# keybored.net
KiCad netlist of a schematic drawn in EAGLE
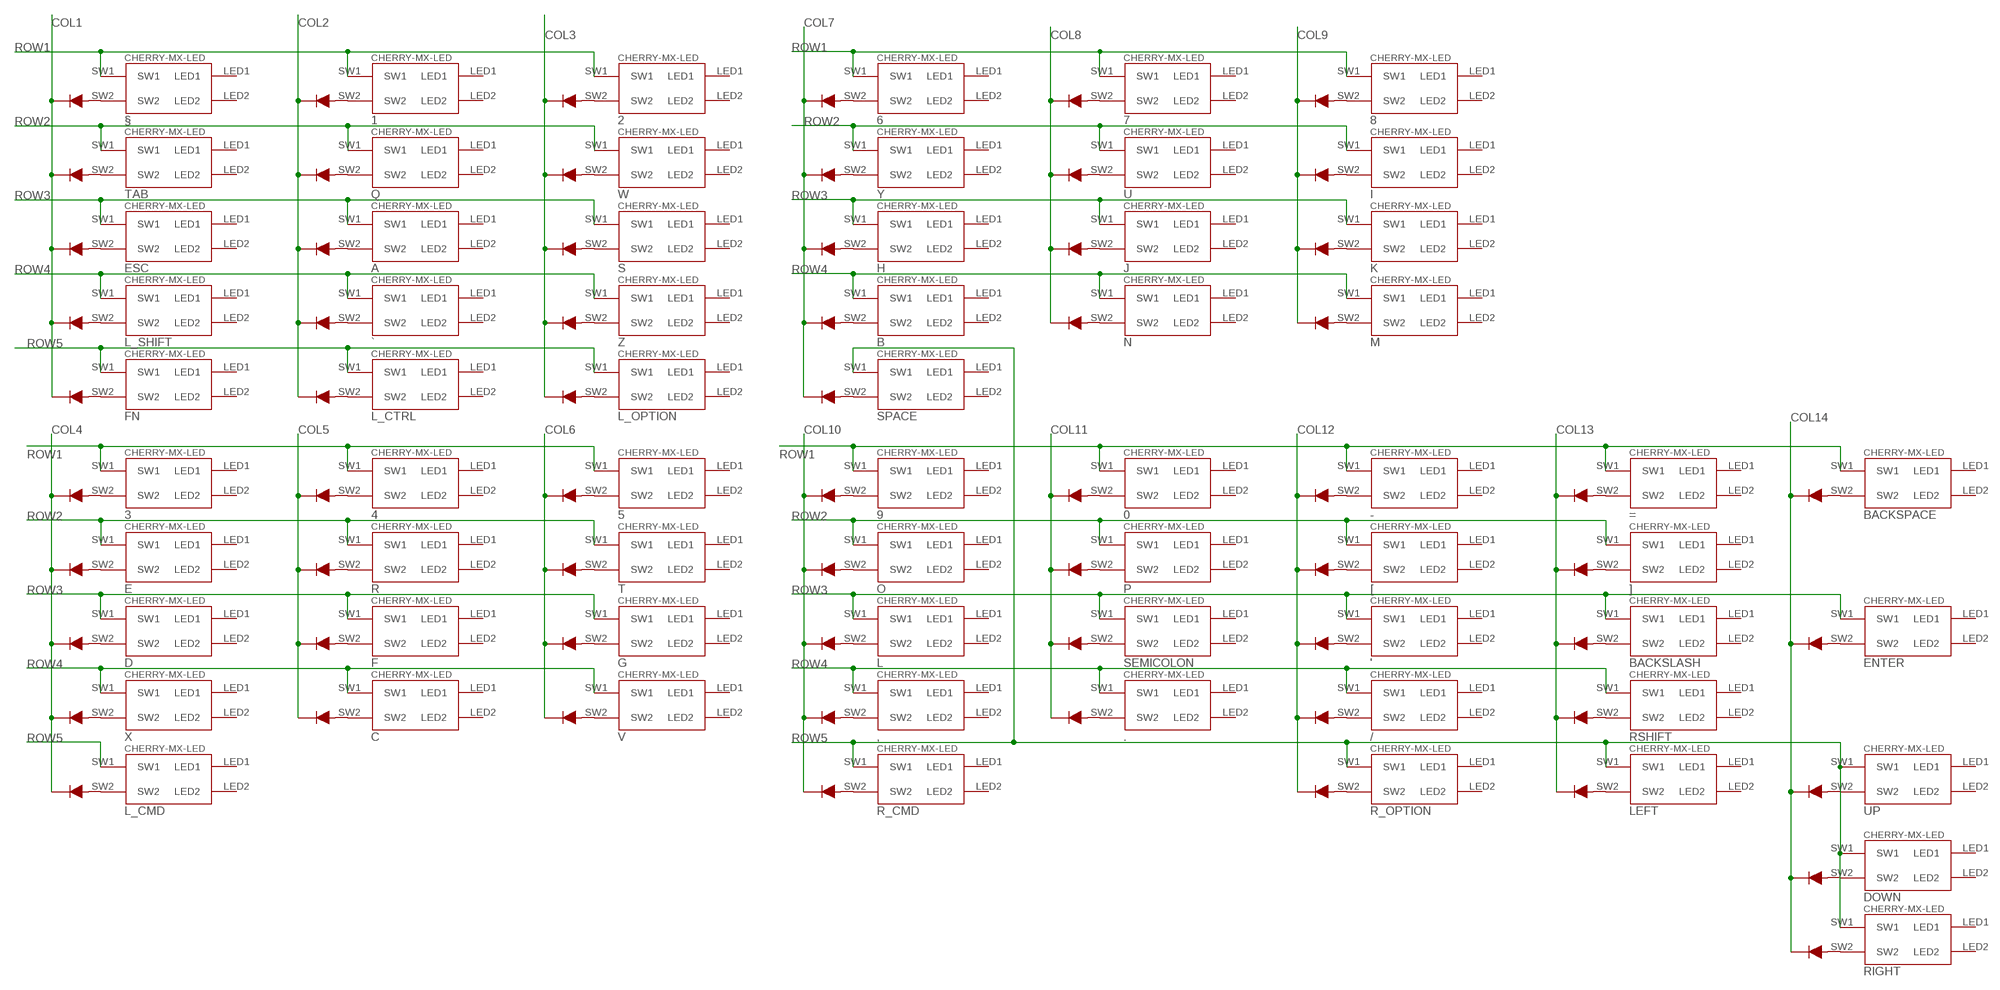
[diagram p0: schematic, sheet 1]

(export (version "E")
  (design (tool "Eeschema 10.0.6"))
  (components
    (comp (ref "'")
      (value "CHERRY-MX-LED")
      (footprint "eagle-import:CHERRY-MX-LED")
      (libsource (lib "eagle-import") (part "CHERRY-MX-LED"))
    )
    (comp (ref ",")
      (value "CHERRY-MX-LED")
      (footprint "eagle-import:CHERRY-MX-LED")
      (libsource (lib "eagle-import") (part "CHERRY-MX-LED"))
    )
    (comp (ref "-")
      (value "CHERRY-MX-LED")
      (footprint "eagle-import:CHERRY-MX-LED")
      (libsource (lib "eagle-import") (part "CHERRY-MX-LED"))
    )
    (comp (ref ".")
      (value "CHERRY-MX-LED")
      (footprint "eagle-import:CHERRY-MX-LED")
      (libsource (lib "eagle-import") (part "CHERRY-MX-LED"))
    )
    (comp (ref "/")
      (value "CHERRY-MX-LED")
      (footprint "eagle-import:CHERRY-MX-LED")
      (libsource (lib "eagle-import") (part "CHERRY-MX-LED"))
    )
    (comp (ref "0")
      (value "CHERRY-MX-LED")
      (footprint "eagle-import:CHERRY-MX-LED")
      (libsource (lib "eagle-import") (part "CHERRY-MX-LED"))
    )
    (comp (ref "1")
      (value "CHERRY-MX-LED")
      (footprint "eagle-import:CHERRY-MX-LED")
      (libsource (lib "eagle-import") (part "CHERRY-MX-LED"))
    )
    (comp (ref "2")
      (value "CHERRY-MX-LED")
      (footprint "eagle-import:CHERRY-MX-LED")
      (libsource (lib "eagle-import") (part "CHERRY-MX-LED"))
    )
    (comp (ref "3")
      (value "CHERRY-MX-LED")
      (footprint "eagle-import:CHERRY-MX-LED")
      (libsource (lib "eagle-import") (part "CHERRY-MX-LED"))
    )
    (comp (ref "4")
      (value "CHERRY-MX-LED")
      (footprint "eagle-import:CHERRY-MX-LED")
      (libsource (lib "eagle-import") (part "CHERRY-MX-LED"))
    )
    (comp (ref "5")
      (value "CHERRY-MX-LED")
      (footprint "eagle-import:CHERRY-MX-LED")
      (libsource (lib "eagle-import") (part "CHERRY-MX-LED"))
    )
    (comp (ref "6")
      (value "CHERRY-MX-LED")
      (footprint "eagle-import:CHERRY-MX-LED")
      (libsource (lib "eagle-import") (part "CHERRY-MX-LED"))
    )
    (comp (ref "7")
      (value "CHERRY-MX-LED")
      (footprint "eagle-import:CHERRY-MX-LED")
      (libsource (lib "eagle-import") (part "CHERRY-MX-LED"))
    )
    (comp (ref "8")
      (value "CHERRY-MX-LED")
      (footprint "eagle-import:CHERRY-MX-LED")
      (libsource (lib "eagle-import") (part "CHERRY-MX-LED"))
    )
    (comp (ref "9")
      (value "CHERRY-MX-LED")
      (footprint "eagle-import:CHERRY-MX-LED")
      (libsource (lib "eagle-import") (part "CHERRY-MX-LED"))
    )
    (comp (ref "=")
      (value "CHERRY-MX-LED")
      (footprint "eagle-import:CHERRY-MX-LED")
      (libsource (lib "eagle-import") (part "CHERRY-MX-LED"))
    )
    (comp (ref "A")
      (value "CHERRY-MX-LED")
      (footprint "eagle-import:CHERRY-MX-LED")
      (libsource (lib "eagle-import") (part "CHERRY-MX-LED"))
    )
    (comp (ref "B")
      (value "CHERRY-MX-LED")
      (footprint "eagle-import:CHERRY-MX-LED")
      (libsource (lib "eagle-import") (part "CHERRY-MX-LED"))
    )
    (comp (ref "BACKSLASH")
      (value "CHERRY-MX-LED")
      (footprint "eagle-import:CHERRY-MX-LED")
      (libsource (lib "eagle-import") (part "CHERRY-MX-LED"))
    )
    (comp (ref "BACKSPACE")
      (value "CHERRY-MX-LED")
      (footprint "eagle-import:CHERRY-MX-LED")
      (libsource (lib "eagle-import") (part "CHERRY-MX-LED"))
    )
    (comp (ref "C")
      (value "CHERRY-MX-LED")
      (footprint "eagle-import:CHERRY-MX-LED")
      (libsource (lib "eagle-import") (part "CHERRY-MX-LED"))
    )
    (comp (ref "D")
      (value "CHERRY-MX-LED")
      (footprint "eagle-import:CHERRY-MX-LED")
      (libsource (lib "eagle-import") (part "CHERRY-MX-LED"))
    )
    (comp (ref "D1")
      (value "DIODE_1N4148W")
      (footprint "eagle-import:SOD123")
      (libsource (lib "eagle-import") (part "DIODE_1N4148W"))
    )
    (comp (ref "D2")
      (value "DIODE_1N4148W")
      (footprint "eagle-import:SOD123")
      (libsource (lib "eagle-import") (part "DIODE_1N4148W"))
    )
    (comp (ref "D3")
      (value "DIODE_1N4148W")
      (footprint "eagle-import:SOD123")
      (libsource (lib "eagle-import") (part "DIODE_1N4148W"))
    )
    (comp (ref "D4")
      (value "DIODE_1N4148W")
      (footprint "eagle-import:SOD123")
      (libsource (lib "eagle-import") (part "DIODE_1N4148W"))
    )
    (comp (ref "D5")
      (value "DIODE_1N4148W")
      (footprint "eagle-import:SOD123")
      (libsource (lib "eagle-import") (part "DIODE_1N4148W"))
    )
    (comp (ref "D6")
      (value "DIODE_1N4148W")
      (footprint "eagle-import:SOD123")
      (libsource (lib "eagle-import") (part "DIODE_1N4148W"))
    )
    (comp (ref "D7")
      (value "DIODE_1N4148W")
      (footprint "eagle-import:SOD123")
      (libsource (lib "eagle-import") (part "DIODE_1N4148W"))
    )
    (comp (ref "D8")
      (value "DIODE_1N4148W")
      (footprint "eagle-import:SOD123")
      (libsource (lib "eagle-import") (part "DIODE_1N4148W"))
    )
    (comp (ref "D9")
      (value "DIODE_1N4148W")
      (footprint "eagle-import:SOD123")
      (libsource (lib "eagle-import") (part "DIODE_1N4148W"))
    )
    (comp (ref "D10")
      (value "DIODE_1N4148W")
      (footprint "eagle-import:SOD123")
      (libsource (lib "eagle-import") (part "DIODE_1N4148W"))
    )
    (comp (ref "D11")
      (value "DIODE_1N4148W")
      (footprint "eagle-import:SOD123")
      (libsource (lib "eagle-import") (part "DIODE_1N4148W"))
    )
    (comp (ref "D12")
      (value "DIODE_1N4148W")
      (footprint "eagle-import:SOD123")
      (libsource (lib "eagle-import") (part "DIODE_1N4148W"))
    )
    (comp (ref "D13")
      (value "DIODE_1N4148W")
      (footprint "eagle-import:SOD123")
      (libsource (lib "eagle-import") (part "DIODE_1N4148W"))
    )
    (comp (ref "D14")
      (value "DIODE_1N4148W")
      (footprint "eagle-import:SOD123")
      (libsource (lib "eagle-import") (part "DIODE_1N4148W"))
    )
    (comp (ref "D15")
      (value "DIODE_1N4148W")
      (footprint "eagle-import:SOD123")
      (libsource (lib "eagle-import") (part "DIODE_1N4148W"))
    )
    (comp (ref "D16")
      (value "DIODE_1N4148W")
      (footprint "eagle-import:SOD123")
      (libsource (lib "eagle-import") (part "DIODE_1N4148W"))
    )
    (comp (ref "D17")
      (value "DIODE_1N4148W")
      (footprint "eagle-import:SOD123")
      (libsource (lib "eagle-import") (part "DIODE_1N4148W"))
    )
    (comp (ref "D18")
      (value "DIODE_1N4148W")
      (footprint "eagle-import:SOD123")
      (libsource (lib "eagle-import") (part "DIODE_1N4148W"))
    )
    (comp (ref "D19")
      (value "DIODE_1N4148W")
      (footprint "eagle-import:SOD123")
      (libsource (lib "eagle-import") (part "DIODE_1N4148W"))
    )
    (comp (ref "D20")
      (value "DIODE_1N4148W")
      (footprint "eagle-import:SOD123")
      (libsource (lib "eagle-import") (part "DIODE_1N4148W"))
    )
    (comp (ref "D21")
      (value "DIODE_1N4148W")
      (footprint "eagle-import:SOD123")
      (libsource (lib "eagle-import") (part "DIODE_1N4148W"))
    )
    (comp (ref "D22")
      (value "DIODE_1N4148W")
      (footprint "eagle-import:SOD123")
      (libsource (lib "eagle-import") (part "DIODE_1N4148W"))
    )
    (comp (ref "D23")
      (value "DIODE_1N4148W")
      (footprint "eagle-import:SOD123")
      (libsource (lib "eagle-import") (part "DIODE_1N4148W"))
    )
    (comp (ref "D24")
      (value "DIODE_1N4148W")
      (footprint "eagle-import:SOD123")
      (libsource (lib "eagle-import") (part "DIODE_1N4148W"))
    )
    (comp (ref "D25")
      (value "DIODE_1N4148W")
      (footprint "eagle-import:SOD123")
      (libsource (lib "eagle-import") (part "DIODE_1N4148W"))
    )
    (comp (ref "D26")
      (value "DIODE_1N4148W")
      (footprint "eagle-import:SOD123")
      (libsource (lib "eagle-import") (part "DIODE_1N4148W"))
    )
    (comp (ref "D27")
      (value "DIODE_1N4148W")
      (footprint "eagle-import:SOD123")
      (libsource (lib "eagle-import") (part "DIODE_1N4148W"))
    )
    (comp (ref "D28")
      (value "DIODE_1N4148W")
      (footprint "eagle-import:SOD123")
      (libsource (lib "eagle-import") (part "DIODE_1N4148W"))
    )
    (comp (ref "D29")
      (value "DIODE_1N4148W")
      (footprint "eagle-import:SOD123")
      (libsource (lib "eagle-import") (part "DIODE_1N4148W"))
    )
    (comp (ref "D30")
      (value "DIODE_1N4148W")
      (footprint "eagle-import:SOD123")
      (libsource (lib "eagle-import") (part "DIODE_1N4148W"))
    )
    (comp (ref "D31")
      (value "DIODE_1N4148W")
      (footprint "eagle-import:SOD123")
      (libsource (lib "eagle-import") (part "DIODE_1N4148W"))
    )
    (comp (ref "D32")
      (value "DIODE_1N4148W")
      (footprint "eagle-import:SOD123")
      (libsource (lib "eagle-import") (part "DIODE_1N4148W"))
    )
    (comp (ref "D33")
      (value "DIODE_1N4148W")
      (footprint "eagle-import:SOD123")
      (libsource (lib "eagle-import") (part "DIODE_1N4148W"))
    )
    (comp (ref "D34")
      (value "DIODE_1N4148W")
      (footprint "eagle-import:SOD123")
      (libsource (lib "eagle-import") (part "DIODE_1N4148W"))
    )
    (comp (ref "D35")
      (value "DIODE_1N4148W")
      (footprint "eagle-import:SOD123")
      (libsource (lib "eagle-import") (part "DIODE_1N4148W"))
    )
    (comp (ref "D36")
      (value "DIODE_1N4148W")
      (footprint "eagle-import:SOD123")
      (libsource (lib "eagle-import") (part "DIODE_1N4148W"))
    )
    (comp (ref "D37")
      (value "DIODE_1N4148W")
      (footprint "eagle-import:SOD123")
      (libsource (lib "eagle-import") (part "DIODE_1N4148W"))
    )
    (comp (ref "D38")
      (value "DIODE_1N4148W")
      (footprint "eagle-import:SOD123")
      (libsource (lib "eagle-import") (part "DIODE_1N4148W"))
    )
    (comp (ref "D39")
      (value "DIODE_1N4148W")
      (footprint "eagle-import:SOD123")
      (libsource (lib "eagle-import") (part "DIODE_1N4148W"))
    )
    (comp (ref "D40")
      (value "DIODE_1N4148W")
      (footprint "eagle-import:SOD123")
      (libsource (lib "eagle-import") (part "DIODE_1N4148W"))
    )
    (comp (ref "D41")
      (value "DIODE_1N4148W")
      (footprint "eagle-import:SOD123")
      (libsource (lib "eagle-import") (part "DIODE_1N4148W"))
    )
    (comp (ref "D42")
      (value "DIODE_1N4148W")
      (footprint "eagle-import:SOD123")
      (libsource (lib "eagle-import") (part "DIODE_1N4148W"))
    )
    (comp (ref "D43")
      (value "DIODE_1N4148W")
      (footprint "eagle-import:SOD123")
      (libsource (lib "eagle-import") (part "DIODE_1N4148W"))
    )
    (comp (ref "D44")
      (value "DIODE_1N4148W")
      (footprint "eagle-import:SOD123")
      (libsource (lib "eagle-import") (part "DIODE_1N4148W"))
    )
    (comp (ref "D45")
      (value "DIODE_1N4148W")
      (footprint "eagle-import:SOD123")
      (libsource (lib "eagle-import") (part "DIODE_1N4148W"))
    )
    (comp (ref "D46")
      (value "DIODE_1N4148W")
      (footprint "eagle-import:SOD123")
      (libsource (lib "eagle-import") (part "DIODE_1N4148W"))
    )
    (comp (ref "D47")
      (value "DIODE_1N4148W")
      (footprint "eagle-import:SOD123")
      (libsource (lib "eagle-import") (part "DIODE_1N4148W"))
    )
    (comp (ref "D48")
      (value "DIODE_1N4148W")
      (footprint "eagle-import:SOD123")
      (libsource (lib "eagle-import") (part "DIODE_1N4148W"))
    )
    (comp (ref "D49")
      (value "DIODE_1N4148W")
      (footprint "eagle-import:SOD123")
      (libsource (lib "eagle-import") (part "DIODE_1N4148W"))
    )
    (comp (ref "D50")
      (value "DIODE_1N4148W")
      (footprint "eagle-import:SOD123")
      (libsource (lib "eagle-import") (part "DIODE_1N4148W"))
    )
    (comp (ref "D51")
      (value "DIODE_1N4148W")
      (footprint "eagle-import:SOD123")
      (libsource (lib "eagle-import") (part "DIODE_1N4148W"))
    )
    (comp (ref "D52")
      (value "DIODE_1N4148W")
      (footprint "eagle-import:SOD123")
      (libsource (lib "eagle-import") (part "DIODE_1N4148W"))
    )
    (comp (ref "D53")
      (value "DIODE_1N4148W")
      (footprint "eagle-import:SOD123")
      (libsource (lib "eagle-import") (part "DIODE_1N4148W"))
    )
    (comp (ref "D54")
      (value "DIODE_1N4148W")
      (footprint "eagle-import:SOD123")
      (libsource (lib "eagle-import") (part "DIODE_1N4148W"))
    )
    (comp (ref "D55")
      (value "DIODE_1N4148W")
      (footprint "eagle-import:SOD123")
      (libsource (lib "eagle-import") (part "DIODE_1N4148W"))
    )
    (comp (ref "D56")
      (value "DIODE_1N4148W")
      (footprint "eagle-import:SOD123")
      (libsource (lib "eagle-import") (part "DIODE_1N4148W"))
    )
    (comp (ref "D57")
      (value "DIODE_1N4148W")
      (footprint "eagle-import:SOD123")
      (libsource (lib "eagle-import") (part "DIODE_1N4148W"))
    )
    (comp (ref "D58")
      (value "DIODE_1N4148W")
      (footprint "eagle-import:SOD123")
      (libsource (lib "eagle-import") (part "DIODE_1N4148W"))
    )
    (comp (ref "D59")
      (value "DIODE_1N4148W")
      (footprint "eagle-import:SOD123")
      (libsource (lib "eagle-import") (part "DIODE_1N4148W"))
    )
    (comp (ref "D60")
      (value "DIODE_1N4148W")
      (footprint "eagle-import:SOD123")
      (libsource (lib "eagle-import") (part "DIODE_1N4148W"))
    )
    (comp (ref "D61")
      (value "DIODE_1N4148W")
      (footprint "eagle-import:SOD123")
      (libsource (lib "eagle-import") (part "DIODE_1N4148W"))
    )
    (comp (ref "D62")
      (value "DIODE_1N4148W")
      (footprint "eagle-import:SOD123")
      (libsource (lib "eagle-import") (part "DIODE_1N4148W"))
    )
    (comp (ref "D63")
      (value "DIODE_1N4148W")
      (footprint "eagle-import:SOD123")
      (libsource (lib "eagle-import") (part "DIODE_1N4148W"))
    )
    (comp (ref "D64")
      (value "DIODE_1N4148W")
      (footprint "eagle-import:SOD123")
      (libsource (lib "eagle-import") (part "DIODE_1N4148W"))
    )
    (comp (ref "D65")
      (value "DIODE_1N4148W")
      (footprint "eagle-import:SOD123")
      (libsource (lib "eagle-import") (part "DIODE_1N4148W"))
    )
    (comp (ref "DOWN")
      (value "CHERRY-MX-LED")
      (footprint "eagle-import:CHERRY-MX-LED")
      (libsource (lib "eagle-import") (part "CHERRY-MX-LED"))
    )
    (comp (ref "E")
      (value "CHERRY-MX-LED")
      (footprint "eagle-import:CHERRY-MX-LED")
      (libsource (lib "eagle-import") (part "CHERRY-MX-LED"))
    )
    (comp (ref "ENTER")
      (value "CHERRY-MX-LED")
      (footprint "eagle-import:CHERRY-MX-LED")
      (libsource (lib "eagle-import") (part "CHERRY-MX-LED"))
    )
    (comp (ref "ESC")
      (value "CHERRY-MX-LED")
      (footprint "eagle-import:CHERRY-MX-LED")
      (libsource (lib "eagle-import") (part "CHERRY-MX-LED"))
    )
    (comp (ref "F")
      (value "CHERRY-MX-LED")
      (footprint "eagle-import:CHERRY-MX-LED")
      (libsource (lib "eagle-import") (part "CHERRY-MX-LED"))
    )
    (comp (ref "FN")
      (value "CHERRY-MX-LED")
      (footprint "eagle-import:CHERRY-MX-LED")
      (libsource (lib "eagle-import") (part "CHERRY-MX-LED"))
    )
    (comp (ref "G")
      (value "CHERRY-MX-LED")
      (footprint "eagle-import:CHERRY-MX-LED")
      (libsource (lib "eagle-import") (part "CHERRY-MX-LED"))
    )
    (comp (ref "H")
      (value "CHERRY-MX-LED")
      (footprint "eagle-import:CHERRY-MX-LED")
      (libsource (lib "eagle-import") (part "CHERRY-MX-LED"))
    )
    (comp (ref "I")
      (value "CHERRY-MX-LED")
      (footprint "eagle-import:CHERRY-MX-LED")
      (libsource (lib "eagle-import") (part "CHERRY-MX-LED"))
    )
    (comp (ref "J")
      (value "CHERRY-MX-LED")
      (footprint "eagle-import:CHERRY-MX-LED")
      (libsource (lib "eagle-import") (part "CHERRY-MX-LED"))
    )
    (comp (ref "K")
      (value "CHERRY-MX-LED")
      (footprint "eagle-import:CHERRY-MX-LED")
      (libsource (lib "eagle-import") (part "CHERRY-MX-LED"))
    )
    (comp (ref "L")
      (value "CHERRY-MX-LED")
      (footprint "eagle-import:CHERRY-MX-LED")
      (libsource (lib "eagle-import") (part "CHERRY-MX-LED"))
    )
    (comp (ref "LEFT")
      (value "CHERRY-MX-LED")
      (footprint "eagle-import:CHERRY-MX-LED")
      (libsource (lib "eagle-import") (part "CHERRY-MX-LED"))
    )
    (comp (ref "L_CMD")
      (value "CHERRY-MX-LED")
      (footprint "eagle-import:CHERRY-MX-LED")
      (libsource (lib "eagle-import") (part "CHERRY-MX-LED"))
    )
    (comp (ref "L_CTRL")
      (value "CHERRY-MX-LED")
      (footprint "eagle-import:CHERRY-MX-LED")
      (libsource (lib "eagle-import") (part "CHERRY-MX-LED"))
    )
    (comp (ref "L_OPTION")
      (value "CHERRY-MX-LED")
      (footprint "eagle-import:CHERRY-MX-LED")
      (libsource (lib "eagle-import") (part "CHERRY-MX-LED"))
    )
    (comp (ref "L_SHIFT")
      (value "CHERRY-MX-LED")
      (footprint "eagle-import:CHERRY-MX-LED")
      (libsource (lib "eagle-import") (part "CHERRY-MX-LED"))
    )
    (comp (ref "M")
      (value "CHERRY-MX-LED")
      (footprint "eagle-import:CHERRY-MX-LED")
      (libsource (lib "eagle-import") (part "CHERRY-MX-LED"))
    )
    (comp (ref "N")
      (value "CHERRY-MX-LED")
      (footprint "eagle-import:CHERRY-MX-LED")
      (libsource (lib "eagle-import") (part "CHERRY-MX-LED"))
    )
    (comp (ref "O")
      (value "CHERRY-MX-LED")
      (footprint "eagle-import:CHERRY-MX-LED")
      (libsource (lib "eagle-import") (part "CHERRY-MX-LED"))
    )
    (comp (ref "P")
      (value "CHERRY-MX-LED")
      (footprint "eagle-import:CHERRY-MX-LED")
      (libsource (lib "eagle-import") (part "CHERRY-MX-LED"))
    )
    (comp (ref "Q")
      (value "CHERRY-MX-LED")
      (footprint "eagle-import:CHERRY-MX-LED")
      (libsource (lib "eagle-import") (part "CHERRY-MX-LED"))
    )
    (comp (ref "R")
      (value "CHERRY-MX-LED")
      (footprint "eagle-import:CHERRY-MX-LED")
      (libsource (lib "eagle-import") (part "CHERRY-MX-LED"))
    )
    (comp (ref "RIGHT")
      (value "CHERRY-MX-LED")
      (footprint "eagle-import:CHERRY-MX-LED")
      (libsource (lib "eagle-import") (part "CHERRY-MX-LED"))
    )
    (comp (ref "RSHIFT")
      (value "CHERRY-MX-LED")
      (footprint "eagle-import:CHERRY-MX-LED")
      (libsource (lib "eagle-import") (part "CHERRY-MX-LED"))
    )
    (comp (ref "R_CMD")
      (value "CHERRY-MX-LED")
      (footprint "eagle-import:CHERRY-MX-LED")
      (libsource (lib "eagle-import") (part "CHERRY-MX-LED"))
    )
    (comp (ref "R_OPTION")
      (value "CHERRY-MX-LED")
      (footprint "eagle-import:CHERRY-MX-LED")
      (libsource (lib "eagle-import") (part "CHERRY-MX-LED"))
    )
    (comp (ref "S")
      (value "CHERRY-MX-LED")
      (footprint "eagle-import:CHERRY-MX-LED")
      (libsource (lib "eagle-import") (part "CHERRY-MX-LED"))
    )
    (comp (ref "SEMICOLON")
      (value "CHERRY-MX-LED")
      (footprint "eagle-import:CHERRY-MX-LED")
      (libsource (lib "eagle-import") (part "CHERRY-MX-LED"))
    )
    (comp (ref "SPACE")
      (value "CHERRY-MX-LED")
      (footprint "eagle-import:CHERRY-MX-LED")
      (libsource (lib "eagle-import") (part "CHERRY-MX-LED"))
    )
    (comp (ref "T")
      (value "CHERRY-MX-LED")
      (footprint "eagle-import:CHERRY-MX-LED")
      (libsource (lib "eagle-import") (part "CHERRY-MX-LED"))
    )
    (comp (ref "TAB")
      (value "CHERRY-MX-LED")
      (footprint "eagle-import:CHERRY-MX-LED")
      (libsource (lib "eagle-import") (part "CHERRY-MX-LED"))
    )
    (comp (ref "U")
      (value "CHERRY-MX-LED")
      (footprint "eagle-import:CHERRY-MX-LED")
      (libsource (lib "eagle-import") (part "CHERRY-MX-LED"))
    )
    (comp (ref "UP")
      (value "CHERRY-MX-LED")
      (footprint "eagle-import:CHERRY-MX-LED")
      (libsource (lib "eagle-import") (part "CHERRY-MX-LED"))
    )
    (comp (ref "V")
      (value "CHERRY-MX-LED")
      (footprint "eagle-import:CHERRY-MX-LED")
      (libsource (lib "eagle-import") (part "CHERRY-MX-LED"))
    )
    (comp (ref "W")
      (value "CHERRY-MX-LED")
      (footprint "eagle-import:CHERRY-MX-LED")
      (libsource (lib "eagle-import") (part "CHERRY-MX-LED"))
    )
    (comp (ref "X")
      (value "CHERRY-MX-LED")
      (footprint "eagle-import:CHERRY-MX-LED")
      (libsource (lib "eagle-import") (part "CHERRY-MX-LED"))
    )
    (comp (ref "Y")
      (value "CHERRY-MX-LED")
      (footprint "eagle-import:CHERRY-MX-LED")
      (libsource (lib "eagle-import") (part "CHERRY-MX-LED"))
    )
    (comp (ref "Z")
      (value "CHERRY-MX-LED")
      (footprint "eagle-import:CHERRY-MX-LED")
      (libsource (lib "eagle-import") (part "CHERRY-MX-LED"))
    )
    (comp (ref "[")
      (value "CHERRY-MX-LED")
      (footprint "eagle-import:CHERRY-MX-LED")
      (libsource (lib "eagle-import") (part "CHERRY-MX-LED"))
    )
    (comp (ref "]")
      (value "CHERRY-MX-LED")
      (footprint "eagle-import:CHERRY-MX-LED")
      (libsource (lib "eagle-import") (part "CHERRY-MX-LED"))
    )
    (comp (ref "`")
      (value "CHERRY-MX-LED")
      (footprint "eagle-import:CHERRY-MX-LED")
      (libsource (lib "eagle-import") (part "CHERRY-MX-LED"))
    )
    (comp (ref "§")
      (value "CHERRY-MX-LED")
      (footprint "eagle-import:CHERRY-MX-LED")
      (libsource (lib "eagle-import") (part "CHERRY-MX-LED"))
    )
  )
  (nets
    (net (code "1") (name "/COL1") (class "Default")
      (node (ref "D1") (pin "P$2") (pinfunction "P$2_P$2") (pintype "bidirectional"))
      (node (ref "D10") (pin "P$2") (pinfunction "P$2_P$2") (pintype "bidirectional"))
      (node (ref "D7") (pin "P$2") (pinfunction "P$2_P$2") (pintype "bidirectional"))
      (node (ref "D8") (pin "P$2") (pinfunction "P$2_P$2") (pintype "bidirectional"))
      (node (ref "D9") (pin "P$2") (pinfunction "P$2_P$2") (pintype "bidirectional"))
    )
    (net (code "2") (name "/COL2") (class "Default")
      (node (ref "D2") (pin "P$2") (pinfunction "P$2_P$2") (pintype "bidirectional"))
      (node (ref "D3") (pin "P$2") (pinfunction "P$2_P$2") (pintype "bidirectional"))
      (node (ref "D4") (pin "P$2") (pinfunction "P$2_P$2") (pintype "bidirectional"))
      (node (ref "D5") (pin "P$2") (pinfunction "P$2_P$2") (pintype "bidirectional"))
      (node (ref "D6") (pin "P$2") (pinfunction "P$2_P$2") (pintype "bidirectional"))
    )
    (net (code "3") (name "/COL3") (class "Default")
      (node (ref "D11") (pin "P$2") (pinfunction "P$2_P$2") (pintype "bidirectional"))
      (node (ref "D12") (pin "P$2") (pinfunction "P$2_P$2") (pintype "bidirectional"))
      (node (ref "D13") (pin "P$2") (pinfunction "P$2_P$2") (pintype "bidirectional"))
      (node (ref "D14") (pin "P$2") (pinfunction "P$2_P$2") (pintype "bidirectional"))
      (node (ref "D15") (pin "P$2") (pinfunction "P$2_P$2") (pintype "bidirectional"))
    )
    (net (code "4") (name "/COL4") (class "Default")
      (node (ref "D26") (pin "P$2") (pinfunction "P$2_P$2") (pintype "bidirectional"))
      (node (ref "D27") (pin "P$2") (pinfunction "P$2_P$2") (pintype "bidirectional"))
      (node (ref "D28") (pin "P$2") (pinfunction "P$2_P$2") (pintype "bidirectional"))
      (node (ref "D29") (pin "P$2") (pinfunction "P$2_P$2") (pintype "bidirectional"))
      (node (ref "D30") (pin "P$2") (pinfunction "P$2_P$2") (pintype "bidirectional"))
    )
    (net (code "5") (name "/COL5") (class "Default")
      (node (ref "D21") (pin "P$2") (pinfunction "P$2_P$2") (pintype "bidirectional"))
      (node (ref "D22") (pin "P$2") (pinfunction "P$2_P$2") (pintype "bidirectional"))
      (node (ref "D23") (pin "P$2") (pinfunction "P$2_P$2") (pintype "bidirectional"))
      (node (ref "D24") (pin "P$2") (pinfunction "P$2_P$2") (pintype "bidirectional"))
    )
    (net (code "6") (name "/COL6") (class "Default")
      (node (ref "D16") (pin "P$2") (pinfunction "P$2_P$2") (pintype "bidirectional"))
      (node (ref "D17") (pin "P$2") (pinfunction "P$2_P$2") (pintype "bidirectional"))
      (node (ref "D18") (pin "P$2") (pinfunction "P$2_P$2") (pintype "bidirectional"))
      (node (ref "D19") (pin "P$2") (pinfunction "P$2_P$2") (pintype "bidirectional"))
    )
    (net (code "7") (name "/COL7") (class "Default")
      (node (ref "D25") (pin "P$2") (pinfunction "P$2_P$2") (pintype "bidirectional"))
      (node (ref "D31") (pin "P$2") (pinfunction "P$2_P$2") (pintype "bidirectional"))
      (node (ref "D32") (pin "P$2") (pinfunction "P$2_P$2") (pintype "bidirectional"))
      (node (ref "D33") (pin "P$2") (pinfunction "P$2_P$2") (pintype "bidirectional"))
      (node (ref "D34") (pin "P$2") (pinfunction "P$2_P$2") (pintype "bidirectional"))
    )
    (net (code "8") (name "/COL8") (class "Default")
      (node (ref "D37") (pin "P$2") (pinfunction "P$2_P$2") (pintype "bidirectional"))
      (node (ref "D38") (pin "P$2") (pinfunction "P$2_P$2") (pintype "bidirectional"))
      (node (ref "D39") (pin "P$2") (pinfunction "P$2_P$2") (pintype "bidirectional"))
      (node (ref "D40") (pin "P$2") (pinfunction "P$2_P$2") (pintype "bidirectional"))
    )
    (net (code "9") (name "/COL9") (class "Default")
      (node (ref "D42") (pin "P$2") (pinfunction "P$2_P$2") (pintype "bidirectional"))
      (node (ref "D43") (pin "P$2") (pinfunction "P$2_P$2") (pintype "bidirectional"))
      (node (ref "D44") (pin "P$2") (pinfunction "P$2_P$2") (pintype "bidirectional"))
      (node (ref "D45") (pin "P$2") (pinfunction "P$2_P$2") (pintype "bidirectional"))
    )
    (net (code "10") (name "/COL10") (class "Default")
      (node (ref "D20") (pin "P$2") (pinfunction "P$2_P$2") (pintype "bidirectional"))
      (node (ref "D46") (pin "P$2") (pinfunction "P$2_P$2") (pintype "bidirectional"))
      (node (ref "D47") (pin "P$2") (pinfunction "P$2_P$2") (pintype "bidirectional"))
      (node (ref "D48") (pin "P$2") (pinfunction "P$2_P$2") (pintype "bidirectional"))
      (node (ref "D49") (pin "P$2") (pinfunction "P$2_P$2") (pintype "bidirectional"))
    )
    (net (code "11") (name "/COL11") (class "Default")
      (node (ref "D52") (pin "P$2") (pinfunction "P$2_P$2") (pintype "bidirectional"))
      (node (ref "D53") (pin "P$2") (pinfunction "P$2_P$2") (pintype "bidirectional"))
      (node (ref "D54") (pin "P$2") (pinfunction "P$2_P$2") (pintype "bidirectional"))
      (node (ref "D55") (pin "P$2") (pinfunction "P$2_P$2") (pintype "bidirectional"))
    )
    (net (code "12") (name "/COL12") (class "Default")
      (node (ref "D35") (pin "P$2") (pinfunction "P$2_P$2") (pintype "bidirectional"))
      (node (ref "D56") (pin "P$2") (pinfunction "P$2_P$2") (pintype "bidirectional"))
      (node (ref "D57") (pin "P$2") (pinfunction "P$2_P$2") (pintype "bidirectional"))
      (node (ref "D58") (pin "P$2") (pinfunction "P$2_P$2") (pintype "bidirectional"))
      (node (ref "D59") (pin "P$2") (pinfunction "P$2_P$2") (pintype "bidirectional"))
    )
    (net (code "13") (name "/COL13") (class "Default")
      (node (ref "D36") (pin "P$2") (pinfunction "P$2_P$2") (pintype "bidirectional"))
      (node (ref "D60") (pin "P$2") (pinfunction "P$2_P$2") (pintype "bidirectional"))
      (node (ref "D61") (pin "P$2") (pinfunction "P$2_P$2") (pintype "bidirectional"))
      (node (ref "D62") (pin "P$2") (pinfunction "P$2_P$2") (pintype "bidirectional"))
      (node (ref "D63") (pin "P$2") (pinfunction "P$2_P$2") (pintype "bidirectional"))
    )
    (net (code "14") (name "/COL14") (class "Default")
      (node (ref "D41") (pin "P$2") (pinfunction "P$2_P$2") (pintype "bidirectional"))
      (node (ref "D50") (pin "P$2") (pinfunction "P$2_P$2") (pintype "bidirectional"))
      (node (ref "D51") (pin "P$2") (pinfunction "P$2_P$2") (pintype "bidirectional"))
      (node (ref "D64") (pin "P$2") (pinfunction "P$2_P$2") (pintype "bidirectional"))
      (node (ref "D65") (pin "P$2") (pinfunction "P$2_P$2") (pintype "bidirectional"))
    )
    (net (code "15") (name "/ROW1") (class "Default")
      (node (ref "-") (pin "SW1") (pinfunction "SW1_SW1") (pintype "bidirectional"))
      (node (ref "0") (pin "SW1") (pinfunction "SW1_SW1") (pintype "bidirectional"))
      (node (ref "1") (pin "SW1") (pinfunction "SW1_SW1") (pintype "bidirectional"))
      (node (ref "2") (pin "SW1") (pinfunction "SW1_SW1") (pintype "bidirectional"))
      (node (ref "3") (pin "SW1") (pinfunction "SW1_SW1") (pintype "bidirectional"))
      (node (ref "4") (pin "SW1") (pinfunction "SW1_SW1") (pintype "bidirectional"))
      (node (ref "5") (pin "SW1") (pinfunction "SW1_SW1") (pintype "bidirectional"))
      (node (ref "6") (pin "SW1") (pinfunction "SW1_SW1") (pintype "bidirectional"))
      (node (ref "7") (pin "SW1") (pinfunction "SW1_SW1") (pintype "bidirectional"))
      (node (ref "8") (pin "SW1") (pinfunction "SW1_SW1") (pintype "bidirectional"))
      (node (ref "9") (pin "SW1") (pinfunction "SW1_SW1") (pintype "bidirectional"))
      (node (ref "=") (pin "SW1") (pinfunction "SW1_SW1") (pintype "bidirectional"))
      (node (ref "BACKSPACE") (pin "SW1") (pinfunction "SW1_SW1") (pintype "bidirectional"))
      (node (ref "§") (pin "SW1") (pinfunction "SW1_SW1") (pintype "bidirectional"))
    )
    (net (code "16") (name "/ROW2") (class "Default")
      (node (ref "E") (pin "SW1") (pinfunction "SW1_SW1") (pintype "bidirectional"))
      (node (ref "I") (pin "SW1") (pinfunction "SW1_SW1") (pintype "bidirectional"))
      (node (ref "O") (pin "SW1") (pinfunction "SW1_SW1") (pintype "bidirectional"))
      (node (ref "P") (pin "SW1") (pinfunction "SW1_SW1") (pintype "bidirectional"))
      (node (ref "Q") (pin "SW1") (pinfunction "SW1_SW1") (pintype "bidirectional"))
      (node (ref "R") (pin "SW1") (pinfunction "SW1_SW1") (pintype "bidirectional"))
      (node (ref "T") (pin "SW1") (pinfunction "SW1_SW1") (pintype "bidirectional"))
      (node (ref "TAB") (pin "SW1") (pinfunction "SW1_SW1") (pintype "bidirectional"))
      (node (ref "U") (pin "SW1") (pinfunction "SW1_SW1") (pintype "bidirectional"))
      (node (ref "W") (pin "SW1") (pinfunction "SW1_SW1") (pintype "bidirectional"))
      (node (ref "Y") (pin "SW1") (pinfunction "SW1_SW1") (pintype "bidirectional"))
      (node (ref "[") (pin "SW1") (pinfunction "SW1_SW1") (pintype "bidirectional"))
      (node (ref "]") (pin "SW1") (pinfunction "SW1_SW1") (pintype "bidirectional"))
    )
    (net (code "17") (name "/ROW3") (class "Default")
      (node (ref "'") (pin "SW1") (pinfunction "SW1_SW1") (pintype "bidirectional"))
      (node (ref "A") (pin "SW1") (pinfunction "SW1_SW1") (pintype "bidirectional"))
      (node (ref "BACKSLASH") (pin "SW1") (pinfunction "SW1_SW1") (pintype "bidirectional"))
      (node (ref "D") (pin "SW1") (pinfunction "SW1_SW1") (pintype "bidirectional"))
      (node (ref "ENTER") (pin "SW1") (pinfunction "SW1_SW1") (pintype "bidirectional"))
      (node (ref "ESC") (pin "SW1") (pinfunction "SW1_SW1") (pintype "bidirectional"))
      (node (ref "F") (pin "SW1") (pinfunction "SW1_SW1") (pintype "bidirectional"))
      (node (ref "G") (pin "SW1") (pinfunction "SW1_SW1") (pintype "bidirectional"))
      (node (ref "H") (pin "SW1") (pinfunction "SW1_SW1") (pintype "bidirectional"))
      (node (ref "J") (pin "SW1") (pinfunction "SW1_SW1") (pintype "bidirectional"))
      (node (ref "K") (pin "SW1") (pinfunction "SW1_SW1") (pintype "bidirectional"))
      (node (ref "L") (pin "SW1") (pinfunction "SW1_SW1") (pintype "bidirectional"))
      (node (ref "S") (pin "SW1") (pinfunction "SW1_SW1") (pintype "bidirectional"))
      (node (ref "SEMICOLON") (pin "SW1") (pinfunction "SW1_SW1") (pintype "bidirectional"))
    )
    (net (code "18") (name "/ROW4") (class "Default")
      (node (ref ",") (pin "SW1") (pinfunction "SW1_SW1") (pintype "bidirectional"))
      (node (ref ".") (pin "SW1") (pinfunction "SW1_SW1") (pintype "bidirectional"))
      (node (ref "/") (pin "SW1") (pinfunction "SW1_SW1") (pintype "bidirectional"))
      (node (ref "B") (pin "SW1") (pinfunction "SW1_SW1") (pintype "bidirectional"))
      (node (ref "C") (pin "SW1") (pinfunction "SW1_SW1") (pintype "bidirectional"))
      (node (ref "L_SHIFT") (pin "SW1") (pinfunction "SW1_SW1") (pintype "bidirectional"))
      (node (ref "M") (pin "SW1") (pinfunction "SW1_SW1") (pintype "bidirectional"))
      (node (ref "N") (pin "SW1") (pinfunction "SW1_SW1") (pintype "bidirectional"))
      (node (ref "RSHIFT") (pin "SW1") (pinfunction "SW1_SW1") (pintype "bidirectional"))
      (node (ref "V") (pin "SW1") (pinfunction "SW1_SW1") (pintype "bidirectional"))
      (node (ref "X") (pin "SW1") (pinfunction "SW1_SW1") (pintype "bidirectional"))
      (node (ref "Z") (pin "SW1") (pinfunction "SW1_SW1") (pintype "bidirectional"))
      (node (ref "`") (pin "SW1") (pinfunction "SW1_SW1") (pintype "bidirectional"))
    )
    (net (code "19") (name "/ROW5") (class "Default")
      (node (ref "DOWN") (pin "SW1") (pinfunction "SW1_SW1") (pintype "bidirectional"))
      (node (ref "FN") (pin "SW1") (pinfunction "SW1_SW1") (pintype "bidirectional"))
      (node (ref "LEFT") (pin "SW1") (pinfunction "SW1_SW1") (pintype "bidirectional"))
      (node (ref "L_CMD") (pin "SW1") (pinfunction "SW1_SW1") (pintype "bidirectional"))
      (node (ref "L_CTRL") (pin "SW1") (pinfunction "SW1_SW1") (pintype "bidirectional"))
      (node (ref "L_OPTION") (pin "SW1") (pinfunction "SW1_SW1") (pintype "bidirectional"))
      (node (ref "RIGHT") (pin "SW1") (pinfunction "SW1_SW1") (pintype "bidirectional"))
      (node (ref "R_CMD") (pin "SW1") (pinfunction "SW1_SW1") (pintype "bidirectional"))
      (node (ref "R_OPTION") (pin "SW1") (pinfunction "SW1_SW1") (pintype "bidirectional"))
      (node (ref "SPACE") (pin "SW1") (pinfunction "SW1_SW1") (pintype "bidirectional"))
      (node (ref "UP") (pin "SW1") (pinfunction "SW1_SW1") (pintype "bidirectional"))
    )
    (net (code "20") (name "Net-('-PadSW2)") (class "Default")
      (node (ref "'") (pin "SW2") (pinfunction "SW2_SW2") (pintype "bidirectional"))
      (node (ref "D58") (pin "P$1") (pinfunction "P$1_P$1") (pintype "bidirectional"))
    )
    (net (code "21") (name "Net-(,-PadSW2)") (class "Default")
      (node (ref ",") (pin "SW2") (pinfunction "SW2_SW2") (pintype "bidirectional"))
      (node (ref "D49") (pin "P$1") (pinfunction "P$1_P$1") (pintype "bidirectional"))
    )
    (net (code "22") (name "Net-(--PadSW2)") (class "Default")
      (node (ref "-") (pin "SW2") (pinfunction "SW2_SW2") (pintype "bidirectional"))
      (node (ref "D56") (pin "P$1") (pinfunction "P$1_P$1") (pintype "bidirectional"))
    )
    (net (code "23") (name "Net-(.-PadSW2)") (class "Default")
      (node (ref ".") (pin "SW2") (pinfunction "SW2_SW2") (pintype "bidirectional"))
      (node (ref "D52") (pin "P$1") (pinfunction "P$1_P$1") (pintype "bidirectional"))
    )
    (net (code "24") (name "Net-(/-PadSW2)") (class "Default")
      (node (ref "/") (pin "SW2") (pinfunction "SW2_SW2") (pintype "bidirectional"))
      (node (ref "D59") (pin "P$1") (pinfunction "P$1_P$1") (pintype "bidirectional"))
    )
    (net (code "25") (name "Net-(0-PadSW2)") (class "Default")
      (node (ref "0") (pin "SW2") (pinfunction "SW2_SW2") (pintype "bidirectional"))
      (node (ref "D55") (pin "P$1") (pinfunction "P$1_P$1") (pintype "bidirectional"))
    )
    (net (code "26") (name "Net-(1-PadSW2)") (class "Default")
      (node (ref "1") (pin "SW2") (pinfunction "SW2_SW2") (pintype "bidirectional"))
      (node (ref "D2") (pin "P$1") (pinfunction "P$1_P$1") (pintype "bidirectional"))
    )
    (net (code "27") (name "Net-(2-PadSW2)") (class "Default")
      (node (ref "2") (pin "SW2") (pinfunction "SW2_SW2") (pintype "bidirectional"))
      (node (ref "D11") (pin "P$1") (pinfunction "P$1_P$1") (pintype "bidirectional"))
    )
    (net (code "28") (name "Net-(3-PadSW2)") (class "Default")
      (node (ref "3") (pin "SW2") (pinfunction "SW2_SW2") (pintype "bidirectional"))
      (node (ref "D26") (pin "P$1") (pinfunction "P$1_P$1") (pintype "bidirectional"))
    )
    (net (code "29") (name "Net-(4-PadSW2)") (class "Default")
      (node (ref "4") (pin "SW2") (pinfunction "SW2_SW2") (pintype "bidirectional"))
      (node (ref "D21") (pin "P$1") (pinfunction "P$1_P$1") (pintype "bidirectional"))
    )
    (net (code "30") (name "Net-(5-PadSW2)") (class "Default")
      (node (ref "5") (pin "SW2") (pinfunction "SW2_SW2") (pintype "bidirectional"))
      (node (ref "D16") (pin "P$1") (pinfunction "P$1_P$1") (pintype "bidirectional"))
    )
    (net (code "31") (name "Net-(6-PadSW2)") (class "Default")
      (node (ref "6") (pin "SW2") (pinfunction "SW2_SW2") (pintype "bidirectional"))
      (node (ref "D31") (pin "P$1") (pinfunction "P$1_P$1") (pintype "bidirectional"))
    )
    (net (code "32") (name "Net-(7-PadSW2)") (class "Default")
      (node (ref "7") (pin "SW2") (pinfunction "SW2_SW2") (pintype "bidirectional"))
      (node (ref "D40") (pin "P$1") (pinfunction "P$1_P$1") (pintype "bidirectional"))
    )
    (net (code "33") (name "Net-(8-PadSW2)") (class "Default")
      (node (ref "8") (pin "SW2") (pinfunction "SW2_SW2") (pintype "bidirectional"))
      (node (ref "D45") (pin "P$1") (pinfunction "P$1_P$1") (pintype "bidirectional"))
    )
    (net (code "34") (name "Net-(9-PadSW2)") (class "Default")
      (node (ref "9") (pin "SW2") (pinfunction "SW2_SW2") (pintype "bidirectional"))
      (node (ref "D46") (pin "P$1") (pinfunction "P$1_P$1") (pintype "bidirectional"))
    )
    (net (code "35") (name "Net-(=-PadSW2)") (class "Default")
      (node (ref "=") (pin "SW2") (pinfunction "SW2_SW2") (pintype "bidirectional"))
      (node (ref "D63") (pin "P$1") (pinfunction "P$1_P$1") (pintype "bidirectional"))
    )
    (net (code "36") (name "Net-(A-PadSW2)") (class "Default")
      (node (ref "A") (pin "SW2") (pinfunction "SW2_SW2") (pintype "bidirectional"))
      (node (ref "D4") (pin "P$1") (pinfunction "P$1_P$1") (pintype "bidirectional"))
    )
    (net (code "37") (name "Net-(B-PadSW2)") (class "Default")
      (node (ref "B") (pin "SW2") (pinfunction "SW2_SW2") (pintype "bidirectional"))
      (node (ref "D34") (pin "P$1") (pinfunction "P$1_P$1") (pintype "bidirectional"))
    )
    (net (code "38") (name "Net-(BACKSLASH-PadSW2)") (class "Default")
      (node (ref "BACKSLASH") (pin "SW2") (pinfunction "SW2_SW2") (pintype "bidirectional"))
      (node (ref "D61") (pin "P$1") (pinfunction "P$1_P$1") (pintype "bidirectional"))
    )
    (net (code "39") (name "Net-(BACKSPACE-PadSW2)") (class "Default")
      (node (ref "BACKSPACE") (pin "SW2") (pinfunction "SW2_SW2") (pintype "bidirectional"))
      (node (ref "D64") (pin "P$1") (pinfunction "P$1_P$1") (pintype "bidirectional"))
    )
    (net (code "40") (name "Net-(C-PadSW2)") (class "Default")
      (node (ref "C") (pin "SW2") (pinfunction "SW2_SW2") (pintype "bidirectional"))
      (node (ref "D24") (pin "P$1") (pinfunction "P$1_P$1") (pintype "bidirectional"))
    )
    (net (code "41") (name "Net-(D-PadSW2)") (class "Default")
      (node (ref "D") (pin "SW2") (pinfunction "SW2_SW2") (pintype "bidirectional"))
      (node (ref "D28") (pin "P$1") (pinfunction "P$1_P$1") (pintype "bidirectional"))
    )
    (net (code "42") (name "Net-(D1-PadP$1)") (class "Default")
      (node (ref "D1") (pin "P$1") (pinfunction "P$1_P$1") (pintype "bidirectional"))
      (node (ref "§") (pin "SW2") (pinfunction "SW2_SW2") (pintype "bidirectional"))
    )
    (net (code "43") (name "Net-(D3-PadP$1)") (class "Default")
      (node (ref "D3") (pin "P$1") (pinfunction "P$1_P$1") (pintype "bidirectional"))
      (node (ref "Q") (pin "SW2") (pinfunction "SW2_SW2") (pintype "bidirectional"))
    )
    (net (code "44") (name "Net-(D5-PadP$1)") (class "Default")
      (node (ref "D5") (pin "P$1") (pinfunction "P$1_P$1") (pintype "bidirectional"))
      (node (ref "`") (pin "SW2") (pinfunction "SW2_SW2") (pintype "bidirectional"))
    )
    (net (code "45") (name "Net-(D6-PadP$1)") (class "Default")
      (node (ref "D6") (pin "P$1") (pinfunction "P$1_P$1") (pintype "bidirectional"))
      (node (ref "L_CTRL") (pin "SW2") (pinfunction "SW2_SW2") (pintype "bidirectional"))
    )
    (net (code "46") (name "Net-(D7-PadP$1)") (class "Default")
      (node (ref "D7") (pin "P$1") (pinfunction "P$1_P$1") (pintype "bidirectional"))
      (node (ref "TAB") (pin "SW2") (pinfunction "SW2_SW2") (pintype "bidirectional"))
    )
    (net (code "47") (name "Net-(D8-PadP$1)") (class "Default")
      (node (ref "D8") (pin "P$1") (pinfunction "P$1_P$1") (pintype "bidirectional"))
      (node (ref "ESC") (pin "SW2") (pinfunction "SW2_SW2") (pintype "bidirectional"))
    )
    (net (code "48") (name "Net-(D9-PadP$1)") (class "Default")
      (node (ref "D9") (pin "P$1") (pinfunction "P$1_P$1") (pintype "bidirectional"))
      (node (ref "L_SHIFT") (pin "SW2") (pinfunction "SW2_SW2") (pintype "bidirectional"))
    )
    (net (code "49") (name "Net-(D10-PadP$1)") (class "Default")
      (node (ref "D10") (pin "P$1") (pinfunction "P$1_P$1") (pintype "bidirectional"))
      (node (ref "FN") (pin "SW2") (pinfunction "SW2_SW2") (pintype "bidirectional"))
    )
    (net (code "50") (name "Net-(D12-PadP$1)") (class "Default")
      (node (ref "D12") (pin "P$1") (pinfunction "P$1_P$1") (pintype "bidirectional"))
      (node (ref "W") (pin "SW2") (pinfunction "SW2_SW2") (pintype "bidirectional"))
    )
    (net (code "51") (name "Net-(D13-PadP$1)") (class "Default")
      (node (ref "D13") (pin "P$1") (pinfunction "P$1_P$1") (pintype "bidirectional"))
      (node (ref "S") (pin "SW2") (pinfunction "SW2_SW2") (pintype "bidirectional"))
    )
    (net (code "52") (name "Net-(D14-PadP$1)") (class "Default")
      (node (ref "D14") (pin "P$1") (pinfunction "P$1_P$1") (pintype "bidirectional"))
      (node (ref "Z") (pin "SW2") (pinfunction "SW2_SW2") (pintype "bidirectional"))
    )
    (net (code "53") (name "Net-(D15-PadP$1)") (class "Default")
      (node (ref "D15") (pin "P$1") (pinfunction "P$1_P$1") (pintype "bidirectional"))
      (node (ref "L_OPTION") (pin "SW2") (pinfunction "SW2_SW2") (pintype "bidirectional"))
    )
    (net (code "54") (name "Net-(D17-PadP$1)") (class "Default")
      (node (ref "D17") (pin "P$1") (pinfunction "P$1_P$1") (pintype "bidirectional"))
      (node (ref "T") (pin "SW2") (pinfunction "SW2_SW2") (pintype "bidirectional"))
    )
    (net (code "55") (name "Net-(D18-PadP$1)") (class "Default")
      (node (ref "D18") (pin "P$1") (pinfunction "P$1_P$1") (pintype "bidirectional"))
      (node (ref "G") (pin "SW2") (pinfunction "SW2_SW2") (pintype "bidirectional"))
    )
    (net (code "56") (name "Net-(D19-PadP$1)") (class "Default")
      (node (ref "D19") (pin "P$1") (pinfunction "P$1_P$1") (pintype "bidirectional"))
      (node (ref "V") (pin "SW2") (pinfunction "SW2_SW2") (pintype "bidirectional"))
    )
    (net (code "57") (name "Net-(D20-PadP$1)") (class "Default")
      (node (ref "D20") (pin "P$1") (pinfunction "P$1_P$1") (pintype "bidirectional"))
      (node (ref "R_CMD") (pin "SW2") (pinfunction "SW2_SW2") (pintype "bidirectional"))
    )
    (net (code "58") (name "Net-(D22-PadP$1)") (class "Default")
      (node (ref "D22") (pin "P$1") (pinfunction "P$1_P$1") (pintype "bidirectional"))
      (node (ref "R") (pin "SW2") (pinfunction "SW2_SW2") (pintype "bidirectional"))
    )
    (net (code "59") (name "Net-(D23-PadP$1)") (class "Default")
      (node (ref "D23") (pin "P$1") (pinfunction "P$1_P$1") (pintype "bidirectional"))
      (node (ref "F") (pin "SW2") (pinfunction "SW2_SW2") (pintype "bidirectional"))
    )
    (net (code "60") (name "Net-(D25-PadP$1)") (class "Default")
      (node (ref "D25") (pin "P$1") (pinfunction "P$1_P$1") (pintype "bidirectional"))
      (node (ref "SPACE") (pin "SW2") (pinfunction "SW2_SW2") (pintype "bidirectional"))
    )
    (net (code "61") (name "Net-(D27-PadP$1)") (class "Default")
      (node (ref "D27") (pin "P$1") (pinfunction "P$1_P$1") (pintype "bidirectional"))
      (node (ref "E") (pin "SW2") (pinfunction "SW2_SW2") (pintype "bidirectional"))
    )
    (net (code "62") (name "Net-(D29-PadP$1)") (class "Default")
      (node (ref "D29") (pin "P$1") (pinfunction "P$1_P$1") (pintype "bidirectional"))
      (node (ref "X") (pin "SW2") (pinfunction "SW2_SW2") (pintype "bidirectional"))
    )
    (net (code "63") (name "Net-(D30-PadP$1)") (class "Default")
      (node (ref "D30") (pin "P$1") (pinfunction "P$1_P$1") (pintype "bidirectional"))
      (node (ref "L_CMD") (pin "SW2") (pinfunction "SW2_SW2") (pintype "bidirectional"))
    )
    (net (code "64") (name "Net-(D32-PadP$1)") (class "Default")
      (node (ref "D32") (pin "P$1") (pinfunction "P$1_P$1") (pintype "bidirectional"))
      (node (ref "Y") (pin "SW2") (pinfunction "SW2_SW2") (pintype "bidirectional"))
    )
    (net (code "65") (name "Net-(D33-PadP$1)") (class "Default")
      (node (ref "D33") (pin "P$1") (pinfunction "P$1_P$1") (pintype "bidirectional"))
      (node (ref "H") (pin "SW2") (pinfunction "SW2_SW2") (pintype "bidirectional"))
    )
    (net (code "66") (name "Net-(D35-PadP$1)") (class "Default")
      (node (ref "D35") (pin "P$1") (pinfunction "P$1_P$1") (pintype "bidirectional"))
      (node (ref "R_OPTION") (pin "SW2") (pinfunction "SW2_SW2") (pintype "bidirectional"))
    )
    (net (code "67") (name "Net-(D36-PadP$1)") (class "Default")
      (node (ref "D36") (pin "P$1") (pinfunction "P$1_P$1") (pintype "bidirectional"))
      (node (ref "LEFT") (pin "SW2") (pinfunction "SW2_SW2") (pintype "bidirectional"))
    )
    (net (code "68") (name "Net-(D37-PadP$1)") (class "Default")
      (node (ref "D37") (pin "P$1") (pinfunction "P$1_P$1") (pintype "bidirectional"))
      (node (ref "N") (pin "SW2") (pinfunction "SW2_SW2") (pintype "bidirectional"))
    )
    (net (code "69") (name "Net-(D38-PadP$1)") (class "Default")
      (node (ref "D38") (pin "P$1") (pinfunction "P$1_P$1") (pintype "bidirectional"))
      (node (ref "J") (pin "SW2") (pinfunction "SW2_SW2") (pintype "bidirectional"))
    )
    (net (code "70") (name "Net-(D39-PadP$1)") (class "Default")
      (node (ref "D39") (pin "P$1") (pinfunction "P$1_P$1") (pintype "bidirectional"))
      (node (ref "U") (pin "SW2") (pinfunction "SW2_SW2") (pintype "bidirectional"))
    )
    (net (code "71") (name "Net-(D41-PadP$1)") (class "Default")
      (node (ref "D41") (pin "P$1") (pinfunction "P$1_P$1") (pintype "bidirectional"))
      (node (ref "UP") (pin "SW2") (pinfunction "SW2_SW2") (pintype "bidirectional"))
    )
    (net (code "72") (name "Net-(D42-PadP$1)") (class "Default")
      (node (ref "D42") (pin "P$1") (pinfunction "P$1_P$1") (pintype "bidirectional"))
      (node (ref "M") (pin "SW2") (pinfunction "SW2_SW2") (pintype "bidirectional"))
    )
    (net (code "73") (name "Net-(D43-PadP$1)") (class "Default")
      (node (ref "D43") (pin "P$1") (pinfunction "P$1_P$1") (pintype "bidirectional"))
      (node (ref "K") (pin "SW2") (pinfunction "SW2_SW2") (pintype "bidirectional"))
    )
    (net (code "74") (name "Net-(D44-PadP$1)") (class "Default")
      (node (ref "D44") (pin "P$1") (pinfunction "P$1_P$1") (pintype "bidirectional"))
      (node (ref "I") (pin "SW2") (pinfunction "SW2_SW2") (pintype "bidirectional"))
    )
    (net (code "75") (name "Net-(D47-PadP$1)") (class "Default")
      (node (ref "D47") (pin "P$1") (pinfunction "P$1_P$1") (pintype "bidirectional"))
      (node (ref "O") (pin "SW2") (pinfunction "SW2_SW2") (pintype "bidirectional"))
    )
    (net (code "76") (name "Net-(D48-PadP$1)") (class "Default")
      (node (ref "D48") (pin "P$1") (pinfunction "P$1_P$1") (pintype "bidirectional"))
      (node (ref "L") (pin "SW2") (pinfunction "SW2_SW2") (pintype "bidirectional"))
    )
    (net (code "77") (name "Net-(D50-PadP$1)") (class "Default")
      (node (ref "D50") (pin "P$1") (pinfunction "P$1_P$1") (pintype "bidirectional"))
      (node (ref "DOWN") (pin "SW2") (pinfunction "SW2_SW2") (pintype "bidirectional"))
    )
    (net (code "78") (name "Net-(D51-PadP$1)") (class "Default")
      (node (ref "D51") (pin "P$1") (pinfunction "P$1_P$1") (pintype "bidirectional"))
      (node (ref "RIGHT") (pin "SW2") (pinfunction "SW2_SW2") (pintype "bidirectional"))
    )
    (net (code "79") (name "Net-(D53-PadP$1)") (class "Default")
      (node (ref "D53") (pin "P$1") (pinfunction "P$1_P$1") (pintype "bidirectional"))
      (node (ref "SEMICOLON") (pin "SW2") (pinfunction "SW2_SW2") (pintype "bidirectional"))
    )
    (net (code "80") (name "Net-(D54-PadP$1)") (class "Default")
      (node (ref "D54") (pin "P$1") (pinfunction "P$1_P$1") (pintype "bidirectional"))
      (node (ref "P") (pin "SW2") (pinfunction "SW2_SW2") (pintype "bidirectional"))
    )
    (net (code "81") (name "Net-(D57-PadP$1)") (class "Default")
      (node (ref "D57") (pin "P$1") (pinfunction "P$1_P$1") (pintype "bidirectional"))
      (node (ref "[") (pin "SW2") (pinfunction "SW2_SW2") (pintype "bidirectional"))
    )
    (net (code "82") (name "Net-(D60-PadP$1)") (class "Default")
      (node (ref "D60") (pin "P$1") (pinfunction "P$1_P$1") (pintype "bidirectional"))
      (node (ref "RSHIFT") (pin "SW2") (pinfunction "SW2_SW2") (pintype "bidirectional"))
    )
    (net (code "83") (name "Net-(D62-PadP$1)") (class "Default")
      (node (ref "D62") (pin "P$1") (pinfunction "P$1_P$1") (pintype "bidirectional"))
      (node (ref "]") (pin "SW2") (pinfunction "SW2_SW2") (pintype "bidirectional"))
    )
    (net (code "84") (name "Net-(D65-PadP$1)") (class "Default")
      (node (ref "D65") (pin "P$1") (pinfunction "P$1_P$1") (pintype "bidirectional"))
      (node (ref "ENTER") (pin "SW2") (pinfunction "SW2_SW2") (pintype "bidirectional"))
    )
    (net (code "85") (name "unconnected-('-PadLED1)") (class "Default")
      (node (ref "'") (pin "LED1") (pinfunction "LED1_LED1") (pintype "bidirectional"))
    )
    (net (code "86") (name "unconnected-('-PadLED2)") (class "Default")
      (node (ref "'") (pin "LED2") (pinfunction "LED2_LED2") (pintype "bidirectional"))
    )
    (net (code "87") (name "unconnected-(,-PadLED1)") (class "Default")
      (node (ref ",") (pin "LED1") (pinfunction "LED1_LED1") (pintype "bidirectional"))
    )
    (net (code "88") (name "unconnected-(,-PadLED2)") (class "Default")
      (node (ref ",") (pin "LED2") (pinfunction "LED2_LED2") (pintype "bidirectional"))
    )
    (net (code "89") (name "unconnected-(--PadLED1)") (class "Default")
      (node (ref "-") (pin "LED1") (pinfunction "LED1_LED1") (pintype "bidirectional"))
    )
    (net (code "90") (name "unconnected-(--PadLED2)") (class "Default")
      (node (ref "-") (pin "LED2") (pinfunction "LED2_LED2") (pintype "bidirectional"))
    )
    (net (code "91") (name "unconnected-(.-PadLED1)") (class "Default")
      (node (ref ".") (pin "LED1") (pinfunction "LED1_LED1") (pintype "bidirectional"))
    )
    (net (code "92") (name "unconnected-(.-PadLED2)") (class "Default")
      (node (ref ".") (pin "LED2") (pinfunction "LED2_LED2") (pintype "bidirectional"))
    )
    (net (code "93") (name "unconnected-(/-PadLED1)") (class "Default")
      (node (ref "/") (pin "LED1") (pinfunction "LED1_LED1") (pintype "bidirectional"))
    )
    (net (code "94") (name "unconnected-(/-PadLED2)") (class "Default")
      (node (ref "/") (pin "LED2") (pinfunction "LED2_LED2") (pintype "bidirectional"))
    )
    (net (code "95") (name "unconnected-(0-PadLED1)") (class "Default")
      (node (ref "0") (pin "LED1") (pinfunction "LED1_LED1") (pintype "bidirectional"))
    )
    (net (code "96") (name "unconnected-(0-PadLED2)") (class "Default")
      (node (ref "0") (pin "LED2") (pinfunction "LED2_LED2") (pintype "bidirectional"))
    )
    (net (code "97") (name "unconnected-(1-PadLED1)") (class "Default")
      (node (ref "1") (pin "LED1") (pinfunction "LED1_LED1") (pintype "bidirectional"))
    )
    (net (code "98") (name "unconnected-(1-PadLED2)") (class "Default")
      (node (ref "1") (pin "LED2") (pinfunction "LED2_LED2") (pintype "bidirectional"))
    )
    (net (code "99") (name "unconnected-(2-PadLED1)") (class "Default")
      (node (ref "2") (pin "LED1") (pinfunction "LED1_LED1") (pintype "bidirectional"))
    )
    (net (code "100") (name "unconnected-(2-PadLED2)") (class "Default")
      (node (ref "2") (pin "LED2") (pinfunction "LED2_LED2") (pintype "bidirectional"))
    )
    (net (code "101") (name "unconnected-(3-PadLED1)") (class "Default")
      (node (ref "3") (pin "LED1") (pinfunction "LED1_LED1") (pintype "bidirectional"))
    )
    (net (code "102") (name "unconnected-(3-PadLED2)") (class "Default")
      (node (ref "3") (pin "LED2") (pinfunction "LED2_LED2") (pintype "bidirectional"))
    )
    (net (code "103") (name "unconnected-(4-PadLED1)") (class "Default")
      (node (ref "4") (pin "LED1") (pinfunction "LED1_LED1") (pintype "bidirectional"))
    )
    (net (code "104") (name "unconnected-(4-PadLED2)") (class "Default")
      (node (ref "4") (pin "LED2") (pinfunction "LED2_LED2") (pintype "bidirectional"))
    )
    (net (code "105") (name "unconnected-(5-PadLED1)") (class "Default")
      (node (ref "5") (pin "LED1") (pinfunction "LED1_LED1") (pintype "bidirectional"))
    )
    (net (code "106") (name "unconnected-(5-PadLED2)") (class "Default")
      (node (ref "5") (pin "LED2") (pinfunction "LED2_LED2") (pintype "bidirectional"))
    )
    (net (code "107") (name "unconnected-(6-PadLED1)") (class "Default")
      (node (ref "6") (pin "LED1") (pinfunction "LED1_LED1") (pintype "bidirectional"))
    )
    (net (code "108") (name "unconnected-(6-PadLED2)") (class "Default")
      (node (ref "6") (pin "LED2") (pinfunction "LED2_LED2") (pintype "bidirectional"))
    )
    (net (code "109") (name "unconnected-(7-PadLED1)") (class "Default")
      (node (ref "7") (pin "LED1") (pinfunction "LED1_LED1") (pintype "bidirectional"))
    )
    (net (code "110") (name "unconnected-(7-PadLED2)") (class "Default")
      (node (ref "7") (pin "LED2") (pinfunction "LED2_LED2") (pintype "bidirectional"))
    )
    (net (code "111") (name "unconnected-(8-PadLED1)") (class "Default")
      (node (ref "8") (pin "LED1") (pinfunction "LED1_LED1") (pintype "bidirectional"))
    )
    (net (code "112") (name "unconnected-(8-PadLED2)") (class "Default")
      (node (ref "8") (pin "LED2") (pinfunction "LED2_LED2") (pintype "bidirectional"))
    )
    (net (code "113") (name "unconnected-(9-PadLED1)") (class "Default")
      (node (ref "9") (pin "LED1") (pinfunction "LED1_LED1") (pintype "bidirectional"))
    )
    (net (code "114") (name "unconnected-(9-PadLED2)") (class "Default")
      (node (ref "9") (pin "LED2") (pinfunction "LED2_LED2") (pintype "bidirectional"))
    )
    (net (code "115") (name "unconnected-(=-PadLED1)") (class "Default")
      (node (ref "=") (pin "LED1") (pinfunction "LED1_LED1") (pintype "bidirectional"))
    )
    (net (code "116") (name "unconnected-(=-PadLED2)") (class "Default")
      (node (ref "=") (pin "LED2") (pinfunction "LED2_LED2") (pintype "bidirectional"))
    )
    (net (code "117") (name "unconnected-(A-PadLED1)") (class "Default")
      (node (ref "A") (pin "LED1") (pinfunction "LED1_LED1") (pintype "bidirectional"))
    )
    (net (code "118") (name "unconnected-(A-PadLED2)") (class "Default")
      (node (ref "A") (pin "LED2") (pinfunction "LED2_LED2") (pintype "bidirectional"))
    )
    (net (code "119") (name "unconnected-(B-PadLED1)") (class "Default")
      (node (ref "B") (pin "LED1") (pinfunction "LED1_LED1") (pintype "bidirectional"))
    )
    (net (code "120") (name "unconnected-(B-PadLED2)") (class "Default")
      (node (ref "B") (pin "LED2") (pinfunction "LED2_LED2") (pintype "bidirectional"))
    )
    (net (code "121") (name "unconnected-(BACKSLASH-PadLED1)") (class "Default")
      (node (ref "BACKSLASH") (pin "LED1") (pinfunction "LED1_LED1") (pintype "bidirectional"))
    )
    (net (code "122") (name "unconnected-(BACKSLASH-PadLED2)") (class "Default")
      (node (ref "BACKSLASH") (pin "LED2") (pinfunction "LED2_LED2") (pintype "bidirectional"))
    )
    (net (code "123") (name "unconnected-(BACKSPACE-PadLED1)") (class "Default")
      (node (ref "BACKSPACE") (pin "LED1") (pinfunction "LED1_LED1") (pintype "bidirectional"))
    )
    (net (code "124") (name "unconnected-(BACKSPACE-PadLED2)") (class "Default")
      (node (ref "BACKSPACE") (pin "LED2") (pinfunction "LED2_LED2") (pintype "bidirectional"))
    )
    (net (code "125") (name "unconnected-(C-PadLED1)") (class "Default")
      (node (ref "C") (pin "LED1") (pinfunction "LED1_LED1") (pintype "bidirectional"))
    )
    (net (code "126") (name "unconnected-(C-PadLED2)") (class "Default")
      (node (ref "C") (pin "LED2") (pinfunction "LED2_LED2") (pintype "bidirectional"))
    )
    (net (code "127") (name "unconnected-(D-PadLED1)") (class "Default")
      (node (ref "D") (pin "LED1") (pinfunction "LED1_LED1") (pintype "bidirectional"))
    )
    (net (code "128") (name "unconnected-(D-PadLED2)") (class "Default")
      (node (ref "D") (pin "LED2") (pinfunction "LED2_LED2") (pintype "bidirectional"))
    )
    (net (code "129") (name "unconnected-(DOWN-PadLED1)") (class "Default")
      (node (ref "DOWN") (pin "LED1") (pinfunction "LED1_LED1") (pintype "bidirectional"))
    )
    (net (code "130") (name "unconnected-(DOWN-PadLED2)") (class "Default")
      (node (ref "DOWN") (pin "LED2") (pinfunction "LED2_LED2") (pintype "bidirectional"))
    )
    (net (code "131") (name "unconnected-(E-PadLED1)") (class "Default")
      (node (ref "E") (pin "LED1") (pinfunction "LED1_LED1") (pintype "bidirectional"))
    )
    (net (code "132") (name "unconnected-(E-PadLED2)") (class "Default")
      (node (ref "E") (pin "LED2") (pinfunction "LED2_LED2") (pintype "bidirectional"))
    )
    (net (code "133") (name "unconnected-(ENTER-PadLED1)") (class "Default")
      (node (ref "ENTER") (pin "LED1") (pinfunction "LED1_LED1") (pintype "bidirectional"))
    )
    (net (code "134") (name "unconnected-(ENTER-PadLED2)") (class "Default")
      (node (ref "ENTER") (pin "LED2") (pinfunction "LED2_LED2") (pintype "bidirectional"))
    )
    (net (code "135") (name "unconnected-(ESC-PadLED1)") (class "Default")
      (node (ref "ESC") (pin "LED1") (pinfunction "LED1_LED1") (pintype "bidirectional"))
    )
    (net (code "136") (name "unconnected-(ESC-PadLED2)") (class "Default")
      (node (ref "ESC") (pin "LED2") (pinfunction "LED2_LED2") (pintype "bidirectional"))
    )
    (net (code "137") (name "unconnected-(F-PadLED1)") (class "Default")
      (node (ref "F") (pin "LED1") (pinfunction "LED1_LED1") (pintype "bidirectional"))
    )
    (net (code "138") (name "unconnected-(F-PadLED2)") (class "Default")
      (node (ref "F") (pin "LED2") (pinfunction "LED2_LED2") (pintype "bidirectional"))
    )
    (net (code "139") (name "unconnected-(FN-PadLED1)") (class "Default")
      (node (ref "FN") (pin "LED1") (pinfunction "LED1_LED1") (pintype "bidirectional"))
    )
    (net (code "140") (name "unconnected-(FN-PadLED2)") (class "Default")
      (node (ref "FN") (pin "LED2") (pinfunction "LED2_LED2") (pintype "bidirectional"))
    )
    (net (code "141") (name "unconnected-(G-PadLED1)") (class "Default")
      (node (ref "G") (pin "LED1") (pinfunction "LED1_LED1") (pintype "bidirectional"))
    )
    (net (code "142") (name "unconnected-(G-PadLED2)") (class "Default")
      (node (ref "G") (pin "LED2") (pinfunction "LED2_LED2") (pintype "bidirectional"))
    )
    (net (code "143") (name "unconnected-(H-PadLED1)") (class "Default")
      (node (ref "H") (pin "LED1") (pinfunction "LED1_LED1") (pintype "bidirectional"))
    )
    (net (code "144") (name "unconnected-(H-PadLED2)") (class "Default")
      (node (ref "H") (pin "LED2") (pinfunction "LED2_LED2") (pintype "bidirectional"))
    )
    (net (code "145") (name "unconnected-(I-PadLED1)") (class "Default")
      (node (ref "I") (pin "LED1") (pinfunction "LED1_LED1") (pintype "bidirectional"))
    )
    (net (code "146") (name "unconnected-(I-PadLED2)") (class "Default")
      (node (ref "I") (pin "LED2") (pinfunction "LED2_LED2") (pintype "bidirectional"))
    )
    (net (code "147") (name "unconnected-(J-PadLED1)") (class "Default")
      (node (ref "J") (pin "LED1") (pinfunction "LED1_LED1") (pintype "bidirectional"))
    )
    (net (code "148") (name "unconnected-(J-PadLED2)") (class "Default")
      (node (ref "J") (pin "LED2") (pinfunction "LED2_LED2") (pintype "bidirectional"))
    )
    (net (code "149") (name "unconnected-(K-PadLED1)") (class "Default")
      (node (ref "K") (pin "LED1") (pinfunction "LED1_LED1") (pintype "bidirectional"))
    )
    (net (code "150") (name "unconnected-(K-PadLED2)") (class "Default")
      (node (ref "K") (pin "LED2") (pinfunction "LED2_LED2") (pintype "bidirectional"))
    )
    (net (code "151") (name "unconnected-(L-PadLED1)") (class "Default")
      (node (ref "L") (pin "LED1") (pinfunction "LED1_LED1") (pintype "bidirectional"))
    )
    (net (code "152") (name "unconnected-(L-PadLED2)") (class "Default")
      (node (ref "L") (pin "LED2") (pinfunction "LED2_LED2") (pintype "bidirectional"))
    )
    (net (code "153") (name "unconnected-(LEFT-PadLED1)") (class "Default")
      (node (ref "LEFT") (pin "LED1") (pinfunction "LED1_LED1") (pintype "bidirectional"))
    )
    (net (code "154") (name "unconnected-(LEFT-PadLED2)") (class "Default")
      (node (ref "LEFT") (pin "LED2") (pinfunction "LED2_LED2") (pintype "bidirectional"))
    )
    (net (code "155") (name "unconnected-(L_CMD-PadLED1)") (class "Default")
      (node (ref "L_CMD") (pin "LED1") (pinfunction "LED1_LED1") (pintype "bidirectional"))
    )
    (net (code "156") (name "unconnected-(L_CMD-PadLED2)") (class "Default")
      (node (ref "L_CMD") (pin "LED2") (pinfunction "LED2_LED2") (pintype "bidirectional"))
    )
    (net (code "157") (name "unconnected-(L_CTRL-PadLED1)") (class "Default")
      (node (ref "L_CTRL") (pin "LED1") (pinfunction "LED1_LED1") (pintype "bidirectional"))
    )
    (net (code "158") (name "unconnected-(L_CTRL-PadLED2)") (class "Default")
      (node (ref "L_CTRL") (pin "LED2") (pinfunction "LED2_LED2") (pintype "bidirectional"))
    )
    (net (code "159") (name "unconnected-(L_OPTION-PadLED1)") (class "Default")
      (node (ref "L_OPTION") (pin "LED1") (pinfunction "LED1_LED1") (pintype "bidirectional"))
    )
    (net (code "160") (name "unconnected-(L_OPTION-PadLED2)") (class "Default")
      (node (ref "L_OPTION") (pin "LED2") (pinfunction "LED2_LED2") (pintype "bidirectional"))
    )
    (net (code "161") (name "unconnected-(L_SHIFT-PadLED1)") (class "Default")
      (node (ref "L_SHIFT") (pin "LED1") (pinfunction "LED1_LED1") (pintype "bidirectional"))
    )
    (net (code "162") (name "unconnected-(L_SHIFT-PadLED2)") (class "Default")
      (node (ref "L_SHIFT") (pin "LED2") (pinfunction "LED2_LED2") (pintype "bidirectional"))
    )
    (net (code "163") (name "unconnected-(M-PadLED1)") (class "Default")
      (node (ref "M") (pin "LED1") (pinfunction "LED1_LED1") (pintype "bidirectional"))
    )
    (net (code "164") (name "unconnected-(M-PadLED2)") (class "Default")
      (node (ref "M") (pin "LED2") (pinfunction "LED2_LED2") (pintype "bidirectional"))
    )
    (net (code "165") (name "unconnected-(N-PadLED1)") (class "Default")
      (node (ref "N") (pin "LED1") (pinfunction "LED1_LED1") (pintype "bidirectional"))
    )
    (net (code "166") (name "unconnected-(N-PadLED2)") (class "Default")
      (node (ref "N") (pin "LED2") (pinfunction "LED2_LED2") (pintype "bidirectional"))
    )
    (net (code "167") (name "unconnected-(O-PadLED1)") (class "Default")
      (node (ref "O") (pin "LED1") (pinfunction "LED1_LED1") (pintype "bidirectional"))
    )
    (net (code "168") (name "unconnected-(O-PadLED2)") (class "Default")
      (node (ref "O") (pin "LED2") (pinfunction "LED2_LED2") (pintype "bidirectional"))
    )
    (net (code "169") (name "unconnected-(P-PadLED1)") (class "Default")
      (node (ref "P") (pin "LED1") (pinfunction "LED1_LED1") (pintype "bidirectional"))
    )
    (net (code "170") (name "unconnected-(P-PadLED2)") (class "Default")
      (node (ref "P") (pin "LED2") (pinfunction "LED2_LED2") (pintype "bidirectional"))
    )
    (net (code "171") (name "unconnected-(Q-PadLED1)") (class "Default")
      (node (ref "Q") (pin "LED1") (pinfunction "LED1_LED1") (pintype "bidirectional"))
    )
    (net (code "172") (name "unconnected-(Q-PadLED2)") (class "Default")
      (node (ref "Q") (pin "LED2") (pinfunction "LED2_LED2") (pintype "bidirectional"))
    )
    (net (code "173") (name "unconnected-(R-PadLED1)") (class "Default")
      (node (ref "R") (pin "LED1") (pinfunction "LED1_LED1") (pintype "bidirectional"))
    )
    (net (code "174") (name "unconnected-(R-PadLED2)") (class "Default")
      (node (ref "R") (pin "LED2") (pinfunction "LED2_LED2") (pintype "bidirectional"))
    )
    (net (code "175") (name "unconnected-(RIGHT-PadLED1)") (class "Default")
      (node (ref "RIGHT") (pin "LED1") (pinfunction "LED1_LED1") (pintype "bidirectional"))
    )
    (net (code "176") (name "unconnected-(RIGHT-PadLED2)") (class "Default")
      (node (ref "RIGHT") (pin "LED2") (pinfunction "LED2_LED2") (pintype "bidirectional"))
    )
    (net (code "177") (name "unconnected-(RSHIFT-PadLED1)") (class "Default")
      (node (ref "RSHIFT") (pin "LED1") (pinfunction "LED1_LED1") (pintype "bidirectional"))
    )
    (net (code "178") (name "unconnected-(RSHIFT-PadLED2)") (class "Default")
      (node (ref "RSHIFT") (pin "LED2") (pinfunction "LED2_LED2") (pintype "bidirectional"))
    )
    (net (code "179") (name "unconnected-(R_CMD-PadLED1)") (class "Default")
      (node (ref "R_CMD") (pin "LED1") (pinfunction "LED1_LED1") (pintype "bidirectional"))
    )
    (net (code "180") (name "unconnected-(R_CMD-PadLED2)") (class "Default")
      (node (ref "R_CMD") (pin "LED2") (pinfunction "LED2_LED2") (pintype "bidirectional"))
    )
    (net (code "181") (name "unconnected-(R_OPTION-PadLED1)") (class "Default")
      (node (ref "R_OPTION") (pin "LED1") (pinfunction "LED1_LED1") (pintype "bidirectional"))
    )
    (net (code "182") (name "unconnected-(R_OPTION-PadLED2)") (class "Default")
      (node (ref "R_OPTION") (pin "LED2") (pinfunction "LED2_LED2") (pintype "bidirectional"))
    )
    (net (code "183") (name "unconnected-(S-PadLED1)") (class "Default")
      (node (ref "S") (pin "LED1") (pinfunction "LED1_LED1") (pintype "bidirectional"))
    )
    (net (code "184") (name "unconnected-(S-PadLED2)") (class "Default")
      (node (ref "S") (pin "LED2") (pinfunction "LED2_LED2") (pintype "bidirectional"))
    )
    (net (code "185") (name "unconnected-(SEMICOLON-PadLED1)") (class "Default")
      (node (ref "SEMICOLON") (pin "LED1") (pinfunction "LED1_LED1") (pintype "bidirectional"))
    )
    (net (code "186") (name "unconnected-(SEMICOLON-PadLED2)") (class "Default")
      (node (ref "SEMICOLON") (pin "LED2") (pinfunction "LED2_LED2") (pintype "bidirectional"))
    )
    (net (code "187") (name "unconnected-(SPACE-PadLED1)") (class "Default")
      (node (ref "SPACE") (pin "LED1") (pinfunction "LED1_LED1") (pintype "bidirectional"))
    )
    (net (code "188") (name "unconnected-(SPACE-PadLED2)") (class "Default")
      (node (ref "SPACE") (pin "LED2") (pinfunction "LED2_LED2") (pintype "bidirectional"))
    )
    (net (code "189") (name "unconnected-(T-PadLED1)") (class "Default")
      (node (ref "T") (pin "LED1") (pinfunction "LED1_LED1") (pintype "bidirectional"))
    )
    (net (code "190") (name "unconnected-(T-PadLED2)") (class "Default")
      (node (ref "T") (pin "LED2") (pinfunction "LED2_LED2") (pintype "bidirectional"))
    )
    (net (code "191") (name "unconnected-(TAB-PadLED1)") (class "Default")
      (node (ref "TAB") (pin "LED1") (pinfunction "LED1_LED1") (pintype "bidirectional"))
    )
    (net (code "192") (name "unconnected-(TAB-PadLED2)") (class "Default")
      (node (ref "TAB") (pin "LED2") (pinfunction "LED2_LED2") (pintype "bidirectional"))
    )
    (net (code "193") (name "unconnected-(U-PadLED1)") (class "Default")
      (node (ref "U") (pin "LED1") (pinfunction "LED1_LED1") (pintype "bidirectional"))
    )
    (net (code "194") (name "unconnected-(U-PadLED2)") (class "Default")
      (node (ref "U") (pin "LED2") (pinfunction "LED2_LED2") (pintype "bidirectional"))
    )
    (net (code "195") (name "unconnected-(UP-PadLED1)") (class "Default")
      (node (ref "UP") (pin "LED1") (pinfunction "LED1_LED1") (pintype "bidirectional"))
    )
    (net (code "196") (name "unconnected-(UP-PadLED2)") (class "Default")
      (node (ref "UP") (pin "LED2") (pinfunction "LED2_LED2") (pintype "bidirectional"))
    )
    (net (code "197") (name "unconnected-(V-PadLED1)") (class "Default")
      (node (ref "V") (pin "LED1") (pinfunction "LED1_LED1") (pintype "bidirectional"))
    )
    (net (code "198") (name "unconnected-(V-PadLED2)") (class "Default")
      (node (ref "V") (pin "LED2") (pinfunction "LED2_LED2") (pintype "bidirectional"))
    )
    (net (code "199") (name "unconnected-(W-PadLED1)") (class "Default")
      (node (ref "W") (pin "LED1") (pinfunction "LED1_LED1") (pintype "bidirectional"))
    )
    (net (code "200") (name "unconnected-(W-PadLED2)") (class "Default")
      (node (ref "W") (pin "LED2") (pinfunction "LED2_LED2") (pintype "bidirectional"))
    )
    (net (code "201") (name "unconnected-(X-PadLED1)") (class "Default")
      (node (ref "X") (pin "LED1") (pinfunction "LED1_LED1") (pintype "bidirectional"))
    )
    (net (code "202") (name "unconnected-(X-PadLED2)") (class "Default")
      (node (ref "X") (pin "LED2") (pinfunction "LED2_LED2") (pintype "bidirectional"))
    )
    (net (code "203") (name "unconnected-(Y-PadLED1)") (class "Default")
      (node (ref "Y") (pin "LED1") (pinfunction "LED1_LED1") (pintype "bidirectional"))
    )
    (net (code "204") (name "unconnected-(Y-PadLED2)") (class "Default")
      (node (ref "Y") (pin "LED2") (pinfunction "LED2_LED2") (pintype "bidirectional"))
    )
    (net (code "205") (name "unconnected-(Z-PadLED1)") (class "Default")
      (node (ref "Z") (pin "LED1") (pinfunction "LED1_LED1") (pintype "bidirectional"))
    )
    (net (code "206") (name "unconnected-(Z-PadLED2)") (class "Default")
      (node (ref "Z") (pin "LED2") (pinfunction "LED2_LED2") (pintype "bidirectional"))
    )
    (net (code "207") (name "unconnected-([-PadLED1)") (class "Default")
      (node (ref "[") (pin "LED1") (pinfunction "LED1_LED1") (pintype "bidirectional"))
    )
    (net (code "208") (name "unconnected-([-PadLED2)") (class "Default")
      (node (ref "[") (pin "LED2") (pinfunction "LED2_LED2") (pintype "bidirectional"))
    )
    (net (code "209") (name "unconnected-(]-PadLED1)") (class "Default")
      (node (ref "]") (pin "LED1") (pinfunction "LED1_LED1") (pintype "bidirectional"))
    )
    (net (code "210") (name "unconnected-(]-PadLED2)") (class "Default")
      (node (ref "]") (pin "LED2") (pinfunction "LED2_LED2") (pintype "bidirectional"))
    )
    (net (code "211") (name "unconnected-(`-PadLED1)") (class "Default")
      (node (ref "`") (pin "LED1") (pinfunction "LED1_LED1") (pintype "bidirectional"))
    )
    (net (code "212") (name "unconnected-(`-PadLED2)") (class "Default")
      (node (ref "`") (pin "LED2") (pinfunction "LED2_LED2") (pintype "bidirectional"))
    )
    (net (code "213") (name "unconnected-(§-PadLED1)") (class "Default")
      (node (ref "§") (pin "LED1") (pinfunction "LED1_LED1") (pintype "bidirectional"))
    )
    (net (code "214") (name "unconnected-(§-PadLED2)") (class "Default")
      (node (ref "§") (pin "LED2") (pinfunction "LED2_LED2") (pintype "bidirectional"))
    )
  )
)
